# TNY268PN_12V_1A_SMPS.net
KiCad netlist of a schematic drawn in Altium Designer
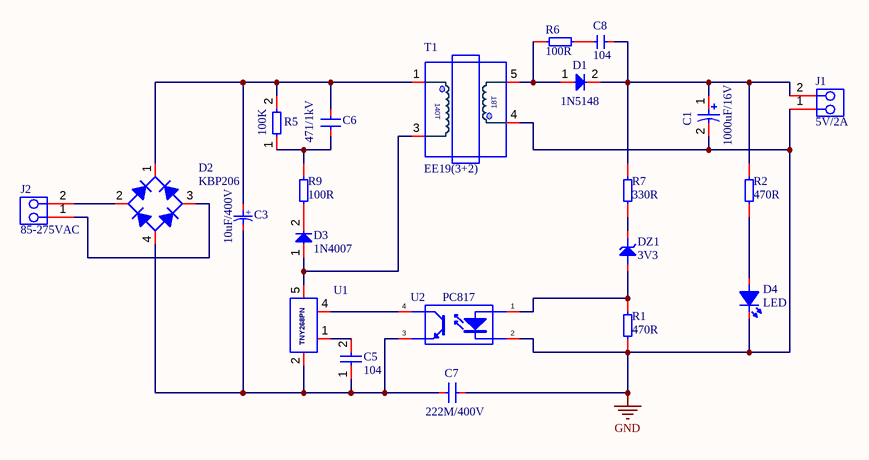
[diagram p0: TNY268PN_12V_1A_SMPS.SchDoc]

(export (version "E")
  (design (tool "Eeschema 10.0.6"))
  (components
    (comp (ref "C1")
      (value "1000uF/16V")
      (footprint "CAP_RAD_3.5mm")
      (libsource (lib "Lib31082020") (part "Capacitor(Radian)"))
    )
    (comp (ref "C3")
      (value "10uF/400V")
      (footprint "CAP_RAD_D10x12.5_POL_BK")
      (libsource (lib "MyAltiumLibrary") (part "Capacitor(Radian)"))
    )
    (comp (ref "C5")
      (value "104")
      (footprint "CAP_Ceramic_Disc_2")
      (libsource (lib "Lib31082020") (part "Capacitors(Disc)"))
    )
    (comp (ref "C6")
      (value "471/1kV")
      (footprint "CAP_DISC_4x3_YL")
      (libsource (lib "MyAltiumLibrary") (part "Capacitors(Disc)"))
    )
    (comp (ref "C7")
      (value "222M/400V")
      (footprint "CAP_DISC_Y2222")
      (libsource (lib "MyAltiumLibrary") (part "Capacitors(Disc)"))
    )
    (comp (ref "C8")
      (value "104")
      (footprint "CAP_Ceramic_Disc_2")
      (libsource (lib "") (part "Capacitors(Disc)_1"))
    )
    (comp (ref "D1")
      (value "1N5148")
      (footprint "DO-41")
      (libsource (lib "MyAltiumLibrary") (part "Diode-1N4007"))
    )
    (comp (ref "D2")
      (value "KBP206")
      (footprint "DIODE-KBP206")
      (libsource (lib "MyAltiumLibrary") (part "Diode-KBP206"))
    )
    (comp (ref "D3")
      (value "1N4007")
      (footprint "DO-41")
      (libsource (lib "MyAltiumLibrary") (part "Diode-1N4007"))
    )
    (comp (ref "D4")
      (value "LED")
      (footprint "LED_3MM_RED")
      (libsource (lib "MyAltiumLibrary") (part "LED 3MM"))
    )
    (comp (ref "DZ1")
      (value "3V3")
      (footprint "DO-35 Horizontal")
      (libsource (lib "MyAltiumLibrary") (part "Diode-Zener"))
    )
    (comp (ref "J1")
      (value "5V/2A")
      (footprint "DG306-5.0-02P-12-00AH")
      (libsource (lib "Lib31082020") (part "DG306-5.0-02P-12-00AH"))
    )
    (comp (ref "J2")
      (value "85-275VAC")
      (footprint "DG127-5.0-02P-14-00AH")
      (libsource (lib "Lib31082020") (part "DG127-5.0-02P-14-00AH"))
    )
    (comp (ref "R1")
      (value "470R")
      (footprint "RES-0.25W-H-MF")
      (libsource (lib "") (part "Resistors THD_1"))
    )
    (comp (ref "R2")
      (value "470R")
      (footprint "RES-0.25W-H-MF")
      (libsource (lib "") (part "Resistors THD_1"))
    )
    (comp (ref "R5")
      (value "100K")
      (footprint "RES-0.25W-H-MF")
      (libsource (lib "Lib31082020") (part "Resistors THD"))
    )
    (comp (ref "R6")
      (value "100R")
      (footprint "RES-0.25W-H-MF")
      (libsource (lib "MyAltiumLibrary") (part "Resistors THD"))
    )
    (comp (ref "R7")
      (value "330R")
      (footprint "RES-0.25W-H-MF")
      (libsource (lib "") (part "Resistors THD_1"))
    )
    (comp (ref "R9")
      (value "100R")
      (footprint "RES-0.25W-H-MF")
      (libsource (lib "") (part "Resistors THD_1"))
    )
    (comp (ref "T1")
      (value "EE19(3+2)")
      (footprint "TRANSFORMER-EE19(3+2)")
      (libsource (lib "MyAltiumLibrary") (part "TRANS-EE19-VERTICAL(3+2)"))
    )
    (comp (ref "U1")
      (value "TNY268PN")
      (footprint "DIP8-TNY268")
      (description "TinySwitch-II: TNY263, TNY264, TNY265, TNY266, TNY267 a TNY268")
      (libsource (lib "Lib31082020") (part "TNY268PN"))
    )
    (comp (ref "U2") (value "PC817") (footprint "DIP4") (libsource (lib "Lib31082020") (part "PC817")))
  )
  (nets
    (net (code "1") (name "GND") (class "Default")
      (node (ref "C1") (pin "2") (pinfunction "2_2") (pintype "passive"))
      (node (ref "C7") (pin "2") (pinfunction "2_2") (pintype "passive"))
      (node (ref "D4") (pin "2") (pinfunction "K_2") (pintype "passive"))
      (node (ref "J1") (pin "1") (pinfunction "1_1") (pintype "passive"))
      (node (ref "R1") (pin "1") (pinfunction "1_1") (pintype "passive"))
      (node (ref "T1") (pin "4") (pinfunction "4_4") (pintype "passive"))
      (node (ref "U2") (pin "2") (pinfunction "K_2") (pintype "passive"))
    )
    (net (code "2") (name "Net-(C1-Pad1)") (class "Default")
      (node (ref "C1") (pin "1") (pinfunction "1_1") (pintype "passive"))
      (node (ref "C8") (pin "2") (pinfunction "2_2") (pintype "passive"))
      (node (ref "D1") (pin "2") (pinfunction "2_2") (pintype "passive"))
      (node (ref "J1") (pin "2") (pinfunction "2_2") (pintype "passive"))
      (node (ref "R2") (pin "2") (pinfunction "2_2") (pintype "passive"))
      (node (ref "R7") (pin "2") (pinfunction "2_2") (pintype "passive"))
    )
    (net (code "3") (name "Net-(C5-Pad2)") (class "Default")
      (node (ref "C5") (pin "2") (pinfunction "2_2") (pintype "passive"))
      (node (ref "U1") (pin "1") (pinfunction "1_1") (pintype "passive"))
    )
    (net (code "4") (name "Net-(C6-Pad1)") (class "Default")
      (node (ref "C6") (pin "1") (pinfunction "1_1") (pintype "passive"))
      (node (ref "R5") (pin "1") (pinfunction "1_1") (pintype "passive"))
      (node (ref "R9") (pin "2") (pinfunction "2_2") (pintype "passive"))
    )
    (net (code "5") (name "Net-(C8-Pad1)") (class "Default")
      (node (ref "C8") (pin "1") (pinfunction "1_1") (pintype "passive"))
      (node (ref "R6") (pin "2") (pinfunction "2_2") (pintype "passive"))
    )
    (net (code "6") (name "Net-(D1-Pad1)") (class "Default")
      (node (ref "D1") (pin "1") (pinfunction "1_1") (pintype "passive"))
      (node (ref "R6") (pin "1") (pinfunction "1_1") (pintype "passive"))
      (node (ref "T1") (pin "5") (pinfunction "5_5") (pintype "passive"))
    )
    (net (code "7") (name "Net-(D2-+)") (class "Default")
      (node (ref "C3") (pin "1") (pinfunction "1_1") (pintype "passive"))
      (node (ref "C6") (pin "2") (pinfunction "2_2") (pintype "passive"))
      (node (ref "D2") (pin "1") (pinfunction "+_1") (pintype "passive"))
      (node (ref "R5") (pin "2") (pinfunction "2_2") (pintype "passive"))
      (node (ref "T1") (pin "1") (pinfunction "1_1") (pintype "passive"))
    )
    (net (code "8") (name "Net-(D2--)") (class "Default")
      (node (ref "C3") (pin "2") (pinfunction "2_2") (pintype "passive"))
      (node (ref "C5") (pin "1") (pinfunction "1_1") (pintype "passive"))
      (node (ref "C7") (pin "1") (pinfunction "1_1") (pintype "passive"))
      (node (ref "D2") (pin "4") (pinfunction "-_4") (pintype "passive"))
      (node (ref "U1") (pin "2") (pinfunction "2_2") (pintype "passive"))
      (node (ref "U2") (pin "3") (pinfunction "E_3") (pintype "passive"))
    )
    (net (code "9") (name "Net-(D2-AC-Pad2)") (class "Default")
      (node (ref "D2") (pin "2") (pinfunction "AC_2") (pintype "passive"))
      (node (ref "J2") (pin "2") (pinfunction "2_2") (pintype "passive"))
    )
    (net (code "10") (name "Net-(D2-AC-Pad3)") (class "Default")
      (node (ref "D2") (pin "3") (pinfunction "AC_3") (pintype "passive"))
      (node (ref "J2") (pin "1") (pinfunction "1_1") (pintype "passive"))
    )
    (net (code "11") (name "Net-(D3-Pad1)") (class "Default")
      (node (ref "D3") (pin "1") (pinfunction "1_1") (pintype "passive"))
      (node (ref "T1") (pin "3") (pinfunction "3_3") (pintype "passive"))
      (node (ref "U1") (pin "5") (pinfunction "5_5") (pintype "passive"))
    )
    (net (code "12") (name "Net-(D3-Pad2)") (class "Default")
      (node (ref "D3") (pin "2") (pinfunction "2_2") (pintype "passive"))
      (node (ref "R9") (pin "1") (pinfunction "1_1") (pintype "passive"))
    )
    (net (code "13") (name "Net-(D4-A)") (class "Default")
      (node (ref "D4") (pin "1") (pinfunction "A_1") (pintype "passive"))
      (node (ref "R2") (pin "1") (pinfunction "1_1") (pintype "passive"))
    )
    (net (code "14") (name "Net-(DZ1-Pad2)") (class "Default")
      (node (ref "DZ1") (pin "2") (pinfunction "2_2") (pintype "passive"))
      (node (ref "R7") (pin "1") (pinfunction "1_1") (pintype "passive"))
    )
    (net (code "15") (name "Net-(U2-A)") (class "Default")
      (node (ref "DZ1") (pin "1") (pinfunction "1_1") (pintype "passive"))
      (node (ref "R1") (pin "2") (pinfunction "2_2") (pintype "passive"))
      (node (ref "U2") (pin "1") (pinfunction "A_1") (pintype "passive"))
    )
    (net (code "16") (name "Net-(U2-C)") (class "Default")
      (node (ref "U1") (pin "4") (pinfunction "4_4") (pintype "passive"))
      (node (ref "U2") (pin "4") (pinfunction "C_4") (pintype "passive"))
    )
  )
)
